# DASH_REGULATORS.net
KiCad netlist of a schematic drawn in Altium Designer
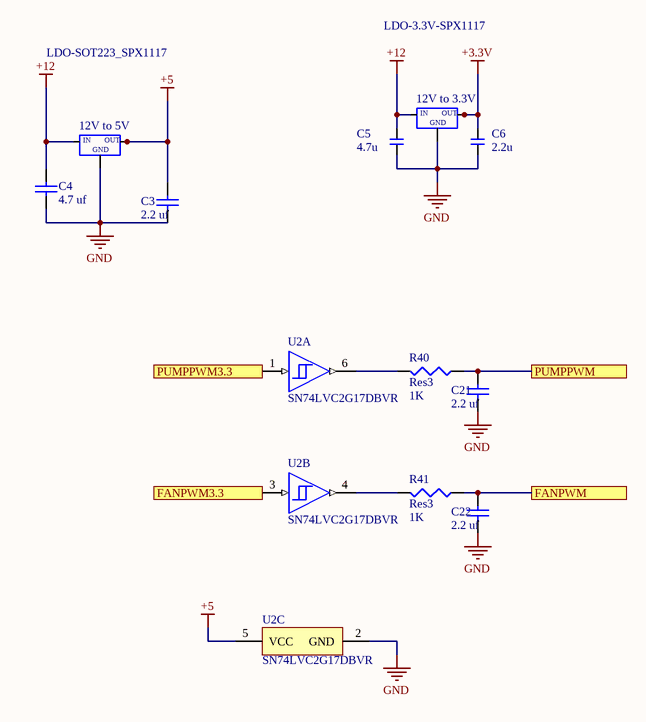
[diagram p0: DASH_REGULATORS.SchDoc]

(export (version "E")
  (design (tool "Eeschema 10.0.6"))
  (components
    (comp (ref "12V to 3.3V")
      (value "LDO-3.3V-SPX1117")
      (footprint "SOT223")
      (libsource (lib "ife19_Elec_Library") (part "LDO-SOT223_SPX1117"))
    )
    (comp (ref "12V to 5V")
      (value "LDO-SOT223_SPX1117")
      (footprint "SOT223")
      (fields (field (name "SOURCE") "ife19_Elec_Library.SchLib"))
      (libsource (lib "Illini Formula Electric") (part "LDO-SOT223_SPX1117"))
    )
    (comp (ref "C3")
      (value "2.2 uf")
      (footprint "CAPC1608X87X35NL15T15")
      (description ".1 uf")
      (fields (field (name "PART NUMBER") "C0603C104J3RAC7867") (field (name "MANUFACTURER") "Kemet"))
      (libsource (lib "Altium Content Vault") (part "CAP"))
    )
    (comp (ref "C4")
      (value "4.7 uf")
      (footprint "CAPC1608X87X35NL15T15")
      (description ".1 uf")
      (fields (field (name "PART NUMBER") "C0603C104J3RAC7867") (field (name "MANUFACTURER") "Kemet"))
      (libsource (lib "Altium Content Vault") (part "CAP"))
    )
    (comp (ref "C5")
      (value "4.7u")
      (footprint "CAP-0603")
      (libsource (lib "ife19_Elec_Library") (part "CAP-0603"))
    )
    (comp (ref "C6")
      (value "2.2u")
      (footprint "CAP-0603")
      (libsource (lib "ife19_Elec_Library") (part "CAP-0603"))
    )
    (comp (ref "C21")
      (value "2.2 uf")
      (footprint "CAPC1608X87X35NL15T15")
      (description ".1 uf")
      (fields (field (name "PART NUMBER") "C0603C104J3RAC7867") (field (name "MANUFACTURER") "Kemet"))
      (libsource (lib "Altium Content Vault") (part "CAP"))
    )
    (comp (ref "C22")
      (value "2.2 uf")
      (footprint "CAPC1608X87X35NL15T15")
      (description ".1 uf")
      (fields (field (name "PART NUMBER") "C0603C104J3RAC7867") (field (name "MANUFACTURER") "Kemet"))
      (libsource (lib "Altium Content Vault") (part "CAP"))
    )
    (comp (ref "R40")
      (value "Res3")
      (footprint "J1-0603")
      (description "Resistor")
      (fields (field (name "ALTIUM_VALUE") "1K") (field (name "PUBLISHER") "Altium Limited"))
      (libsource (lib "Miscellaneous Devices") (part "Res3"))
    )
    (comp (ref "R41")
      (value "Res3")
      (footprint "J1-0603")
      (description "Resistor")
      (fields (field (name "ALTIUM_VALUE") "1K") (field (name "PUBLISHER") "Altium Limited"))
      (libsource (lib "Miscellaneous Devices") (part "Res3"))
    )
    (comp (ref "U2")
      (value "SN74LVC2G17DBVR")
      (footprint "DBV0006A_N")
      (description "Dual Schmitt-Trigger Buffer, DBV0006A, LARGE T&R")
      (fields
        (field (name "GENERIC PART NUMBER") "SN74LVC2G17")
        (field (name "MANUFACTURER") "Texas Instruments")
      )
      (libsource (lib "Altium Content Vault") (part "TI-SN74XXX2GXXX-6_A-SCHMITT"))
    )
  )
  (nets
    (net (code "1") (name "+3.3V") (class "Default")
      (node (ref "12V to 3.3V") (pin "2") (pinfunction "2_2") (pintype "passive"))
      (node (ref "12V to 3.3V") (pin "4") (pinfunction "4_4") (pintype "passive"))
      (node (ref "C6") (pin "2") (pinfunction "2_2") (pintype "passive"))
    )
    (net (code "2") (name "+5") (class "Default")
      (node (ref "12V to 5V") (pin "2") (pinfunction "2_2") (pintype "passive"))
      (node (ref "12V to 5V") (pin "4") (pinfunction "4_4") (pintype "passive"))
      (node (ref "C3") (pin "2") (pinfunction "2_2") (pintype "passive"))
      (node (ref "U2") (pin "5") (pinfunction "VCC_5") (pintype "power_in"))
    )
    (net (code "3") (name "+12") (class "Default")
      (node (ref "12V to 3.3V") (pin "3") (pinfunction "3_3") (pintype "passive"))
      (node (ref "12V to 5V") (pin "3") (pinfunction "3_3") (pintype "passive"))
      (node (ref "C4") (pin "2") (pinfunction "2_2") (pintype "passive"))
      (node (ref "C5") (pin "2") (pinfunction "2_2") (pintype "passive"))
    )
    (net (code "4") (name "/FANPWM") (class "Default")
      (node (ref "C22") (pin "2") (pinfunction "2_2") (pintype "passive"))
      (node (ref "R41") (pin "1") (pinfunction "1_1") (pintype "passive"))
    )
    (net (code "5") (name "/FANPWM3.3") (class "Default")
      (node (ref "U2") (pin "3") (pinfunction "2A_3") (pintype "input"))
    )
    (net (code "6") (name "/PUMPPWM") (class "Default")
      (node (ref "C21") (pin "2") (pinfunction "2_2") (pintype "passive"))
      (node (ref "R40") (pin "1") (pinfunction "1_1") (pintype "passive"))
    )
    (net (code "7") (name "/PUMPPWM3.3") (class "Default")
      (node (ref "U2") (pin "1") (pinfunction "1A_1") (pintype "input"))
    )
    (net (code "8") (name "GND") (class "Default")
      (node (ref "12V to 3.3V") (pin "1") (pinfunction "1_1") (pintype "passive"))
      (node (ref "12V to 5V") (pin "1") (pinfunction "1_1") (pintype "passive"))
      (node (ref "C21") (pin "1") (pinfunction "1_1") (pintype "passive"))
      (node (ref "C22") (pin "1") (pinfunction "1_1") (pintype "passive"))
      (node (ref "C3") (pin "1") (pinfunction "1_1") (pintype "passive"))
      (node (ref "C4") (pin "1") (pinfunction "1_1") (pintype "passive"))
      (node (ref "C5") (pin "1") (pinfunction "1_1") (pintype "passive"))
      (node (ref "C6") (pin "1") (pinfunction "1_1") (pintype "passive"))
      (node (ref "U2") (pin "2") (pinfunction "GND_2") (pintype "power_in"))
    )
    (net (code "9") (name "Net-(U2A-1Y)") (class "Default")
      (node (ref "R40") (pin "2") (pinfunction "2_2") (pintype "passive"))
      (node (ref "U2") (pin "6") (pinfunction "1Y_6") (pintype "output"))
    )
    (net (code "10") (name "Net-(U2B-2Y)") (class "Default")
      (node (ref "R41") (pin "2") (pinfunction "2_2") (pintype "passive"))
      (node (ref "U2") (pin "4") (pinfunction "2Y_4") (pintype "output"))
    )
  )
)
